# User_Interface.net
KiCad netlist of a schematic drawn in Altium Designer
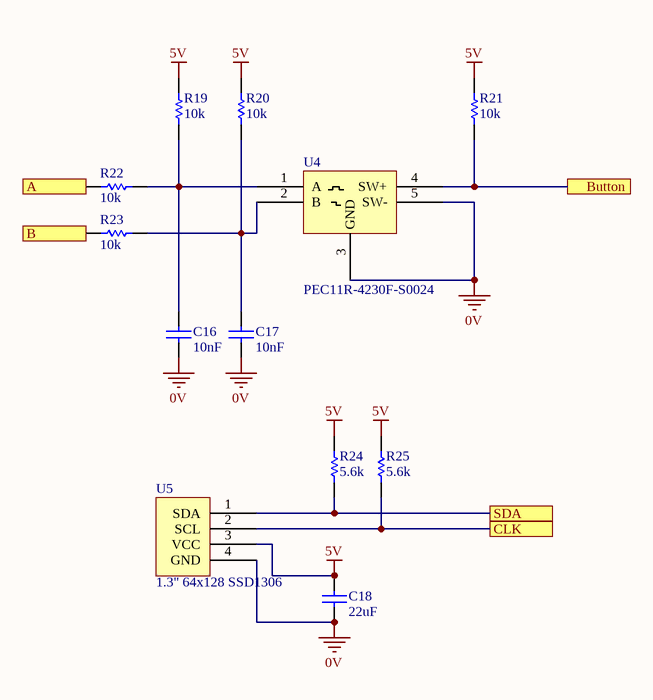
[diagram p0: User Interface.SchDoc]

(export (version "E")
  (design (tool "Eeschema 10.0.6"))
  (components
    (comp (ref "C16")
      (value "10nF")
      (footprint "0805")
      (fields
        (field (name "PART NUMBER") "GCM2195C1H103JA16D")
        (field (name "TOLERANCE") "±5%")
        (field (name "MANUFACTURER") "muRata")
      )
      (libsource (lib "ts_20-standard-library") (part "Capacitor"))
    )
    (comp (ref "C17")
      (value "10nF")
      (footprint "0805")
      (fields
        (field (name "PART NUMBER") "GCM2195C1H103JA16D")
        (field (name "TOLERANCE") "±5%")
        (field (name "MANUFACTURER") "muRata")
      )
      (libsource (lib "ts_20-standard-library") (part "Capacitor"))
    )
    (comp (ref "C18")
      (value "22uF")
      (footprint "1206")
      (fields
        (field (name "PART NUMBER") "CC1206MKX5R7BB226")
        (field (name "TOLERANCE") "20%")
        (field (name "MANUFACTURER") "YAGEO")
      )
      (libsource (lib "ts_20-standard-library") (part "Capacitor"))
    )
    (comp (ref "R19")
      (value "10k")
      (footprint "0805")
      (fields
        (field (name "PART NUMBER") "RC0805FR0710KL")
        (field (name "MANUFACTURER") "YAGEO")
        (field (name "TOLERANCE") "0.01")
      )
      (libsource (lib "ts_20-standard-library") (part "Resistor"))
    )
    (comp (ref "R20")
      (value "10k")
      (footprint "0805")
      (fields
        (field (name "PART NUMBER") "RC0805FR0710KL")
        (field (name "MANUFACTURER") "YAGEO")
        (field (name "TOLERANCE") "0.01")
      )
      (libsource (lib "ts_20-standard-library") (part "Resistor"))
    )
    (comp (ref "R21")
      (value "10k")
      (footprint "0805")
      (fields
        (field (name "PART NUMBER") "RC0805FR0710KL")
        (field (name "MANUFACTURER") "YAGEO")
        (field (name "TOLERANCE") "0.01")
      )
      (libsource (lib "ts_20-standard-library") (part "Resistor"))
    )
    (comp (ref "R22")
      (value "10k")
      (footprint "0805")
      (fields
        (field (name "PART NUMBER") "RC0805FR0710KL")
        (field (name "MANUFACTURER") "YAGEO")
        (field (name "TOLERANCE") "0.01")
      )
      (libsource (lib "ts_20-standard-library") (part "Resistor"))
    )
    (comp (ref "R23")
      (value "10k")
      (footprint "0805")
      (fields
        (field (name "PART NUMBER") "RC0805FR0710KL")
        (field (name "MANUFACTURER") "YAGEO")
        (field (name "TOLERANCE") "0.01")
      )
      (libsource (lib "ts_20-standard-library") (part "Resistor"))
    )
    (comp (ref "R24")
      (value "5.6k")
      (footprint "0805")
      (fields
        (field (name "PART NUMBER") "RC0805FR075K6L")
        (field (name "MANUFACTURER") "YAGEO")
        (field (name "TOLERANCE") "0.01")
      )
      (libsource (lib "ts_20-standard-library") (part "Resistor"))
    )
    (comp (ref "R25")
      (value "5.6k")
      (footprint "0805")
      (fields
        (field (name "PART NUMBER") "RC0805FR075K6L")
        (field (name "MANUFACTURER") "YAGEO")
        (field (name "TOLERANCE") "0.01")
      )
      (libsource (lib "ts_20-standard-library") (part "Resistor"))
    )
    (comp (ref "U4")
      (value "PEC11R-4230F-S0024")
      (footprint "PEC11R-4230F-S0024-ND")
      (description "Quadrature Rotary encoder w/ pushbutton")
      (fields
        (field (name "MANUFACTURER") "Bourns Inc.")
        (field (name "DIGIKEY PART NUMBER") "PEC11R-4230F-S0024-ND")
      )
      (libsource (lib "ts_20-standard-library") (part "PEC11R-4230F-S0024-ND"))
    )
    (comp (ref "U5")
      (value "1.3\" 64x128 SSD1306")
      (footprint "1.3\" 64x128 SSD1306")
      (description "1.3\" I2C OLED display using SSD1306 Driver")
      (fields (field (name "MANUFACTURER") "IIC"))
      (libsource (lib "ts_20-standard-library") (part "SSD1306"))
    )
  )
  (nets
    (net (code "1") (name "/A") (class "Default")
      (node (ref "R22") (pin "1") (pinfunction "1_1") (pintype "passive"))
    )
    (net (code "2") (name "/B") (class "Default")
      (node (ref "R23") (pin "1") (pinfunction "1_1") (pintype "passive"))
    )
    (net (code "3") (name "/Button") (class "Default")
      (node (ref "R21") (pin "1") (pinfunction "1_1") (pintype "passive"))
      (node (ref "U4") (pin "4") (pinfunction "SW+_4") (pintype "power_in"))
    )
    (net (code "4") (name "/CLK") (class "Default")
      (node (ref "R25") (pin "1") (pinfunction "1_1") (pintype "passive"))
      (node (ref "U5") (pin "2") (pinfunction "SCL_2") (pintype "passive"))
    )
    (net (code "5") (name "/SDA") (class "Default")
      (node (ref "R24") (pin "1") (pinfunction "1_1") (pintype "passive"))
      (node (ref "U5") (pin "1") (pinfunction "SDA_1") (pintype "passive"))
    )
    (net (code "6") (name "0V") (class "Default")
      (node (ref "C16") (pin "1") (pinfunction "1_1") (pintype "passive"))
      (node (ref "C17") (pin "1") (pinfunction "1_1") (pintype "passive"))
      (node (ref "C18") (pin "1") (pinfunction "1_1") (pintype "passive"))
      (node (ref "U4") (pin "3") (pinfunction "GND_3") (pintype "power_in"))
      (node (ref "U4") (pin "5") (pinfunction "SW-_5") (pintype "power_in"))
      (node (ref "U5") (pin "4") (pinfunction "GND_4") (pintype "passive"))
    )
    (net (code "7") (name "5V") (class "Default")
      (node (ref "C18") (pin "2") (pinfunction "2_2") (pintype "passive"))
      (node (ref "R19") (pin "2") (pinfunction "2_2") (pintype "passive"))
      (node (ref "R20") (pin "2") (pinfunction "2_2") (pintype "passive"))
      (node (ref "R21") (pin "2") (pinfunction "2_2") (pintype "passive"))
      (node (ref "R24") (pin "2") (pinfunction "2_2") (pintype "passive"))
      (node (ref "R25") (pin "2") (pinfunction "2_2") (pintype "passive"))
      (node (ref "U5") (pin "3") (pinfunction "VCC_3") (pintype "passive"))
    )
    (net (code "8") (name "Net-(U4-A)") (class "Default")
      (node (ref "C16") (pin "2") (pinfunction "2_2") (pintype "passive"))
      (node (ref "R19") (pin "1") (pinfunction "1_1") (pintype "passive"))
      (node (ref "R22") (pin "2") (pinfunction "2_2") (pintype "passive"))
      (node (ref "U4") (pin "1") (pinfunction "A_1") (pintype "power_in"))
    )
    (net (code "9") (name "Net-(U4-B)") (class "Default")
      (node (ref "C17") (pin "2") (pinfunction "2_2") (pintype "passive"))
      (node (ref "R20") (pin "1") (pinfunction "1_1") (pintype "passive"))
      (node (ref "R23") (pin "2") (pinfunction "2_2") (pintype "passive"))
      (node (ref "U4") (pin "2") (pinfunction "B_2") (pintype "power_in"))
    )
  )
)
